# CurrentSrc.net
KiCad netlist of a schematic drawn in Altium Designer
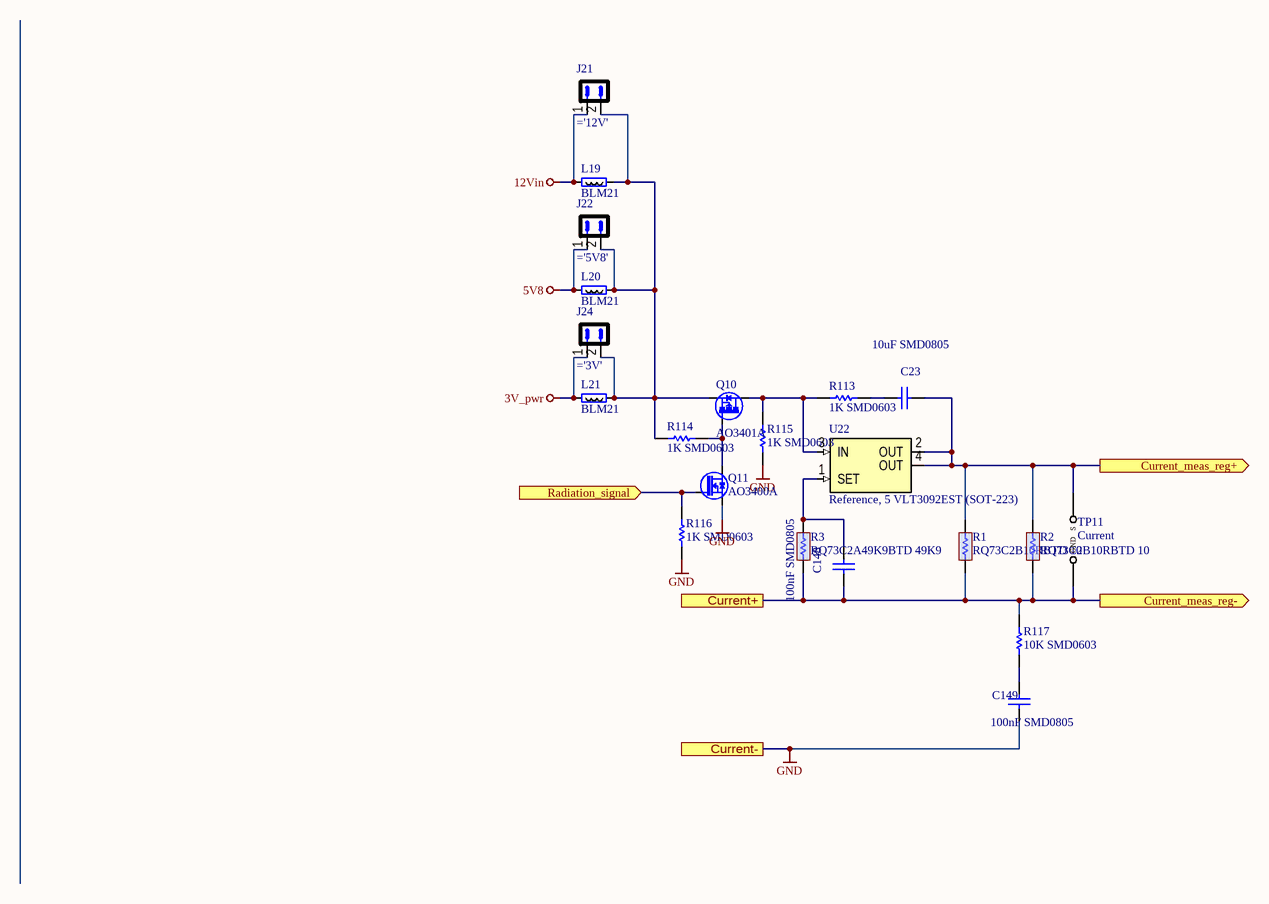
[diagram p0: CurrentSrc.SchDoc]

(export (version "E")
  (design (tool "Eeschema 10.0.6"))
  (components
    (comp (ref "C23")
      (value "10uF SMD0805")
      (footprint "RESC2012X50N")
      (description "Capacitor 0805")
      (libsource (lib "hall_crossboard_1_1") (part "C0805"))
    )
    (comp (ref "C148")
      (value "100nF SMD0805")
      (footprint "RESC2012X50N")
      (description "Capacitor 0805")
      (libsource (lib "hall_crossboard_1_1") (part "C0805"))
    )
    (comp (ref "C149")
      (value "100nF SMD0805")
      (footprint "RESC2012X50N")
      (description "Capacitor 0805")
      (libsource (lib "hall_crossboard_1_1") (part "C0805"))
    )
    (comp (ref "J21")
      (value "12V")
      (footprint "footprint_hall_crossboard_1_1_library:SAMTEC_TSW-102-23-L-S")
      (description "PLS2")
      (fields (field (name "PARTNUMBER") "DS1021-1x2"))
      (libsource (lib "hall_crossboard_1_1") (part "PLS2"))
    )
    (comp (ref "J22")
      (value "5V8")
      (footprint "footprint_hall_crossboard_1_1_library:SAMTEC_TSW-102-23-L-S")
      (description "PLS2")
      (fields (field (name "PARTNUMBER") "DS1021-1x2"))
      (libsource (lib "hall_crossboard_1_1") (part "PLS2"))
    )
    (comp (ref "J24")
      (value "3V")
      (footprint "footprint_hall_crossboard_1_1_library:SAMTEC_TSW-102-23-L-S")
      (description "PLS2")
      (fields (field (name "PARTNUMBER") "DS1021-1x2"))
      (libsource (lib "hall_crossboard_1_1") (part "PLS2"))
    )
    (comp (ref "L19")
      (value "BLM21")
      (footprint "footprint_hall_crossboard_1_1_library:RESC2012X50N")
      (description "SMD Ferrite bead 0805")
      (libsource (lib "hall_crossboard_1_1") (part "BLM21"))
    )
    (comp (ref "L20")
      (value "BLM21")
      (footprint "footprint_hall_crossboard_1_1_library:RESC2012X50N")
      (description "SMD Ferrite bead 0805")
      (libsource (lib "hall_crossboard_1_1") (part "BLM21"))
    )
    (comp (ref "L21")
      (value "BLM21")
      (footprint "footprint_hall_crossboard_1_1_library:RESC2012X50N")
      (description "SMD Ferrite bead 0805")
      (libsource (lib "hall_crossboard_1_1") (part "BLM21"))
    )
    (comp (ref "Q10")
      (value "AO3401A")
      (footprint "SOT95P229X119-3N")
      (description "PMOS")
      (fields (field (name "VOLTAGE") "-30V"))
      (libsource (lib "hall_crossboard_1_1_library") (part "AO3401A"))
    )
    (comp (ref "Q11")
      (value "AO3400A")
      (footprint "SOT95P229X119-3N")
      (description "NMOS")
      (fields (field (name "VOLTAGE") "30V"))
      (libsource (lib "hall_crossboard_1_1_library") (part "AO3400A"))
    )
    (comp (ref "R1")
      (value "RQ73C2B10RBTD 10")
      (footprint "RC1206_0805")
      (description "Precision Resistor, Thin Film, 1206, .4 W, 10 ohm, .1 %, ±10 ppm/°C")
      (fields (field (name "MP") "RQ73C2B10RBTD"))
      (libsource (lib "c1-12") (part "RQ73C2B10RBTD"))
    )
    (comp (ref "R2")
      (value "RQ73C2B10RBTD 10")
      (footprint "RC1206_0805")
      (description "Precision Resistor, Thin Film, 1206, .4 W, 10 ohm, .1 %, ±10 ppm/°C")
      (fields (field (name "MP") "RQ73C2B10RBTD"))
      (libsource (lib "c1-12") (part "RQ73C2B10RBTD"))
    )
    (comp (ref "R3")
      (value "RQ73C2A49K9BTD 49K9")
      (footprint "RESC2012X50N")
      (description "Precision Resistor, Thin Film, 0805, .2 W, 49.9K ohm, .1 %, ±10 ppm/°C")
      (fields (field (name "MP") "RQ73C2A49K9BTD"))
      (libsource (lib "c1-12") (part "RQ73C2A49K9BTD"))
    )
    (comp (ref "R113")
      (value "1K SMD0603")
      (footprint "footprint_hall_crossboard_1_1_library:0603R")
      (description "Resistor 0603")
      (libsource (lib "hall_crossboard_1_1") (part "R0603"))
    )
    (comp (ref "R114")
      (value "1K SMD0603")
      (footprint "footprint_hall_crossboard_1_1_library:0603R")
      (description "Resistor 0603")
      (libsource (lib "hall_crossboard_1_1") (part "R0603"))
    )
    (comp (ref "R115")
      (value "1K SMD0603")
      (footprint "footprint_hall_crossboard_1_1_library:0603R")
      (description "Resistor 0603")
      (libsource (lib "hall_crossboard_1_1") (part "R0603"))
    )
    (comp (ref "R116")
      (value "1K SMD0603")
      (footprint "footprint_hall_crossboard_1_1_library:0603R")
      (description "Resistor 0603")
      (libsource (lib "hall_crossboard_1_1") (part "R0603"))
    )
    (comp (ref "R117")
      (value "10K SMD0603")
      (footprint "footprint_hall_crossboard_1_1_library:0603R")
      (description "Resistor 0603")
      (libsource (lib "hall_crossboard_1_1") (part "R0603"))
    )
    (comp (ref "TP11")
      (value "Current")
      (footprint "footprint_hall_crossboard_1_1_library:TP2")
      (description "Контрольная точка для подключения осциллографа короткой землёй")
      (libsource (lib "schematic_hall_crossboard_1_1_library") (part "OscTP"))
    )
    (comp (ref "U22")
      (value "Reference, 5 VLT3092EST (SOT-223)")
      (footprint "footprint_hall_crossboard_1_1_library:SOT223")
      (description "Reference, 5 V")
      (fields (field (name "TOLERANCE") "1%") (field (name "VOLTAGE") "max 40V"))
      (libsource (lib "schematic_hall_crossboard_1_1_library") (part "LT3092"))
    )
  )
  (nets
    (net (code "1") (name "/Current+") (class "Default")
      (node (ref "C148") (pin "1") (pinfunction "1_1") (pintype "passive"))
      (node (ref "R1") (pin "1") (pinfunction "1_1") (pintype "passive"))
      (node (ref "R117") (pin "2") (pinfunction "2_2") (pintype "passive"))
      (node (ref "R2") (pin "1") (pinfunction "1_1") (pintype "passive"))
      (node (ref "R3") (pin "1") (pinfunction "1_1") (pintype "passive"))
      (node (ref "TP11") (pin "2") (pinfunction "GND_2") (pintype "passive"))
    )
    (net (code "2") (name "/Current_meas_reg+") (class "Default")
      (node (ref "C23") (pin "2") (pinfunction "2_2") (pintype "passive"))
      (node (ref "R1") (pin "2") (pinfunction "2_2") (pintype "passive"))
      (node (ref "R2") (pin "2") (pinfunction "2_2") (pintype "passive"))
      (node (ref "TP11") (pin "1") (pinfunction "S_1") (pintype "passive"))
      (node (ref "U22") (pin "2") (pinfunction "OUT_2") (pintype "power_in"))
      (node (ref "U22") (pin "4") (pinfunction "OUT_4") (pintype "power_in"))
    )
    (net (code "3") (name "/Radiation_signal") (class "Default")
      (node (ref "Q11") (pin "1") (pinfunction "G_1") (pintype "passive"))
      (node (ref "R116") (pin "2") (pinfunction "2_2") (pintype "passive"))
    )
    (net (code "4") (name "3V_pwr") (class "Default")
      (node (ref "J24") (pin "1") (pinfunction "1_1") (pintype "bidirectional"))
      (node (ref "L21") (pin "2") (pinfunction "2_2") (pintype "passive"))
    )
    (net (code "5") (name "5V8") (class "Default")
      (node (ref "J22") (pin "1") (pinfunction "1_1") (pintype "bidirectional"))
      (node (ref "L20") (pin "2") (pinfunction "2_2") (pintype "passive"))
    )
    (net (code "6") (name "12Vin") (class "Default")
      (node (ref "J21") (pin "1") (pinfunction "1_1") (pintype "bidirectional"))
      (node (ref "L19") (pin "2") (pinfunction "2_2") (pintype "passive"))
    )
    (net (code "7") (name "GND") (class "Default")
      (node (ref "C149") (pin "1") (pinfunction "1_1") (pintype "passive"))
      (node (ref "Q11") (pin "2") (pinfunction "S_2") (pintype "passive"))
      (node (ref "R115") (pin "1") (pinfunction "1_1") (pintype "passive"))
      (node (ref "R116") (pin "1") (pinfunction "1_1") (pintype "passive"))
    )
    (net (code "8") (name "Net-(C23-Pad1)") (class "Default")
      (node (ref "C23") (pin "1") (pinfunction "1_1") (pintype "passive"))
      (node (ref "R113") (pin "2") (pinfunction "2_2") (pintype "passive"))
    )
    (net (code "9") (name "Net-(C149-Pad2)") (class "Default")
      (node (ref "C149") (pin "2") (pinfunction "2_2") (pintype "passive"))
      (node (ref "R117") (pin "1") (pinfunction "1_1") (pintype "passive"))
    )
    (net (code "10") (name "Net-(Q10-D)") (class "Default")
      (node (ref "Q10") (pin "3") (pinfunction "D_3") (pintype "passive"))
      (node (ref "R113") (pin "1") (pinfunction "1_1") (pintype "passive"))
      (node (ref "R115") (pin "2") (pinfunction "2_2") (pintype "passive"))
      (node (ref "U22") (pin "3") (pinfunction "IN_3") (pintype "input"))
    )
    (net (code "11") (name "Net-(Q10-G)") (class "Default")
      (node (ref "Q10") (pin "1") (pinfunction "G_1") (pintype "passive"))
      (node (ref "Q11") (pin "3") (pinfunction "D_3") (pintype "passive"))
      (node (ref "R114") (pin "2") (pinfunction "2_2") (pintype "passive"))
    )
    (net (code "12") (name "Net-(Q10-S)") (class "Default")
      (node (ref "J21") (pin "2") (pinfunction "2_2") (pintype "bidirectional"))
      (node (ref "J22") (pin "2") (pinfunction "2_2") (pintype "bidirectional"))
      (node (ref "J24") (pin "2") (pinfunction "2_2") (pintype "bidirectional"))
      (node (ref "L19") (pin "1") (pinfunction "1_1") (pintype "passive"))
      (node (ref "L20") (pin "1") (pinfunction "1_1") (pintype "passive"))
      (node (ref "L21") (pin "1") (pinfunction "1_1") (pintype "passive"))
      (node (ref "Q10") (pin "2") (pinfunction "S_2") (pintype "passive"))
      (node (ref "R114") (pin "1") (pinfunction "1_1") (pintype "passive"))
    )
    (net (code "13") (name "Net-(U22-SET)") (class "Default")
      (node (ref "C148") (pin "2") (pinfunction "2_2") (pintype "passive"))
      (node (ref "R3") (pin "2") (pinfunction "2_2") (pintype "passive"))
      (node (ref "U22") (pin "1") (pinfunction "SET_1") (pintype "input"))
    )
  )
)
